# Sheet1.net
KiCad netlist of a schematic drawn in Altium Designer
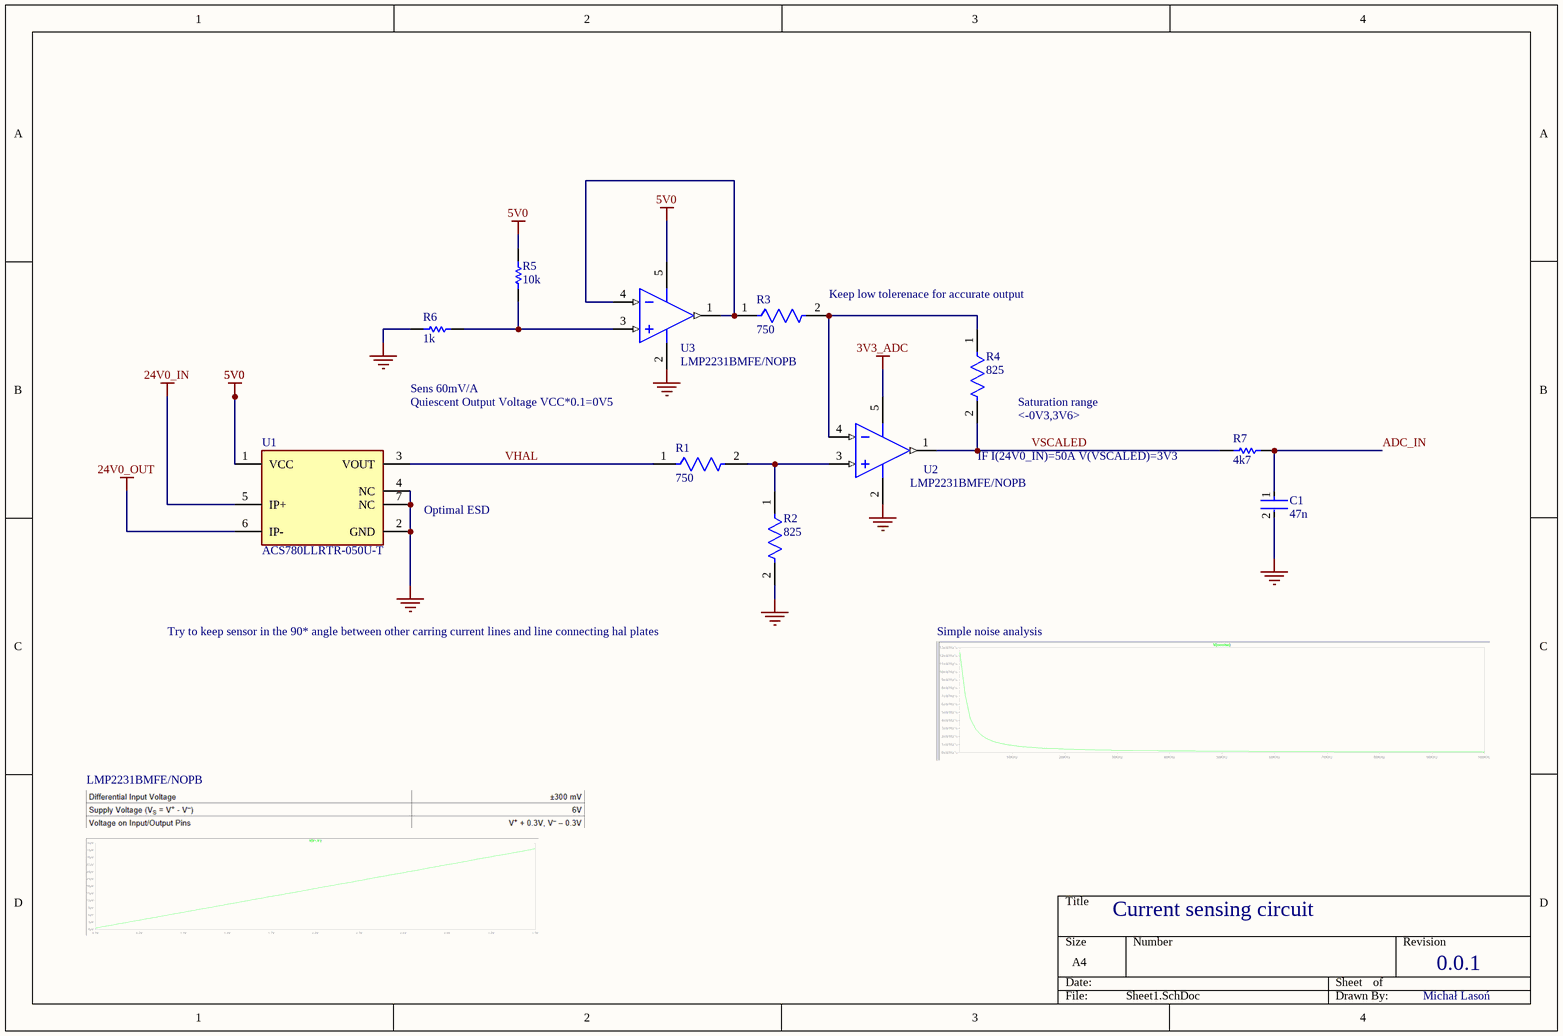
[diagram p0: Sheet1.SchDoc]

(export (version "E")
  (design (tool "Eeschema 10.0.6"))
  (components
    (comp (ref "C1")
      (value "47n")
      (footprint "FP-0805-L_2_01_0_2-W_1_25-MFG")
      (description "General Purpose Ceramic Capacitor, 0805, 47nF, 10%, X8R, 15%, 50V")
      (fields (field (name "VOLTAGE") "50V") (field (name "TOLERANCE") "10%"))
      (libsource (lib "Altium Content Vault") (part "02cd4be3c70576c341d710602a673aa"))
    )
    (comp (ref "R1")
      (value "750")
      (footprint "FP-RP73P-1J-MFG")
      (description "RES SMD 750 OHM 0.1% 1/6W 0603")
      (fields (field (name "TOLERANCE") "0.001") (field (name "MANUFACTURER PART NUMBER") "RP73PF1J750RBTDF"))
      (libsource (lib "Altium Content Vault") (part "1029c3af85768c4190bb7ad29bc67b5"))
    )
    (comp (ref "R2")
      (value "825")
      (footprint "FP-RP73P-1J-MFG")
      (description "RES SMD 825 OHM 0.1% 1/6W 0603")
      (fields
        (field (name "MANUFACTURER") "TE Connectivity")
        (field (name "OCTOPART") "https://octopart.com/rp73pf1j825rbtdf-te+connectivity-45466269")
      )
      (libsource (lib "Altium Content Vault") (part "1029c3af85768c4190bb7ad29bc67b5"))
    )
    (comp (ref "R3")
      (value "750")
      (footprint "FP-RP73P-1J-MFG")
      (description "RES SMD 750 OHM 0.1% 1/6W 0603")
      (fields (field (name "TOLERANCE") "0.001") (field (name "MANUFACTURER PART NUMBER") "RP73PF1J750RBTDF"))
      (libsource (lib "Altium Content Vault") (part "1029c3af85768c4190bb7ad29bc67b5"))
    )
    (comp (ref "R4")
      (value "825")
      (footprint "FP-RP73P-1J-MFG")
      (description "RES SMD 825 OHM 0.1% 1/6W 0603")
      (fields
        (field (name "MANUFACTURER") "TE Connectivity")
        (field (name "OCTOPART") "https://octopart.com/rp73pf1j825rbtdf-te+connectivity-45466269")
      )
      (libsource (lib "Altium Content Vault") (part "1029c3af85768c4190bb7ad29bc67b5"))
    )
    (comp (ref "R5")
      (value "10k")
      (footprint "RESC1609X50X30NL8T20")
      (description "Chip Resistor, 10 KOhm, +/- 1%, 100 mW, -55 to 155 degC, 0603 (1608 Metric), RoHS, Tape and Reel")
      (fields (field (name "MANUFACTURER") "Vishay Semiconductor"))
      (libsource (lib "Altium Content Vault") (part "RES-2"))
    )
    (comp (ref "R6")
      (value "1k")
      (footprint "RESC1608X55X30LL15T15")
      (fields (field (name "PART NUMBER") "ERJ-3EKF1001V") (field (name "MANUFACTURER") "Panasonic"))
      (libsource (lib "Altium Content Vault") (part "RES"))
    )
    (comp (ref "R7")
      (value "4k7")
      (footprint "YAGO-RC0805_M")
      (fields
        (field (name "TOLERANCE") "+/- 1%")
        (field (name "PARTNUMBER") "RC0805FR-074K7L")
        (field (name "POWER") "0.125 W")
      )
      (libsource (lib "Altium Content Vault") (part "YAGO-RES-2"))
    )
    (comp (ref "U1")
      (value "ACS780LLRTR-050U-T")
      (footprint "FP-LR-7-MFG")
      (description "HIGH-PRECISION LINEAR HALL-EFFEC")
      (libsource (lib "Altium Content Vault") (part "e7dc1a95c8c68bde7436943aa9e0c70"))
    )
    (comp (ref "U2")
      (value "LMP2231BMFE/NOPB")
      (footprint "DBV0005A_L")
      (description "Single Micropower, 1.6V, Precision Operational Amplifier with CMOS Inputs, 5-pin SOT-23, Pb-Free")
      (fields (field (name "MANUFACTURER") "Texas Instruments"))
      (libsource (lib "Altium Content Vault") (part "AMP-OPA-LM7121-5"))
    )
    (comp (ref "U3")
      (value "LMP2231BMFE/NOPB")
      (footprint "DBV0005A_L")
      (description "Single Micropower, 1.6V, Precision Operational Amplifier with CMOS Inputs, 5-pin SOT-23, Pb-Free")
      (fields (field (name "MANUFACTURER") "Texas Instruments"))
      (libsource (lib "Altium Content Vault") (part "AMP-OPA-LM7121-5"))
    )
  )
  (nets
    (net (code "1") (name "/ADC_IN") (class "Default")
      (node (ref "C1") (pin "1") (pinfunction "1_1") (pintype "passive"))
      (node (ref "R7") (pin "2") (pinfunction "2_2") (pintype "passive"))
    )
    (net (code "2") (name "/VHAL") (class "Default")
      (node (ref "R1") (pin "1") (pinfunction "1_1") (pintype "passive"))
      (node (ref "U1") (pin "3") (pinfunction "VOUT_3") (pintype "passive"))
    )
    (net (code "3") (name "/VSCALED") (class "Default")
      (node (ref "R4") (pin "2") (pinfunction "2_2") (pintype "passive"))
      (node (ref "R7") (pin "1") (pinfunction "1_1") (pintype "passive"))
      (node (ref "U2") (pin "1") (pinfunction "OUT_1") (pintype "output"))
    )
    (net (code "4") (name "3V3_ADC") (class "Default")
      (node (ref "U2") (pin "5") (pinfunction "V+_5") (pintype "power_in"))
    )
    (net (code "5") (name "5V0") (class "Default")
      (node (ref "R5") (pin "2") (pinfunction "2_2") (pintype "passive"))
      (node (ref "U1") (pin "1") (pinfunction "VCC_1") (pintype "power_in"))
      (node (ref "U3") (pin "5") (pinfunction "V+_5") (pintype "power_in"))
    )
    (net (code "6") (name "24V0_IN") (class "Default")
      (node (ref "U1") (pin "5") (pinfunction "IP+_5") (pintype "passive"))
    )
    (net (code "7") (name "24V0_OUT") (class "Default")
      (node (ref "U1") (pin "6") (pinfunction "IP-_6") (pintype "passive"))
    )
    (net (code "8") (name "GND") (class "Default")
      (node (ref "C1") (pin "2") (pinfunction "2_2") (pintype "passive"))
      (node (ref "R2") (pin "2") (pinfunction "2_2") (pintype "passive"))
      (node (ref "R6") (pin "1") (pinfunction "1_1") (pintype "passive"))
      (node (ref "U1") (pin "2") (pinfunction "GND_2") (pintype "power_in"))
      (node (ref "U1") (pin "4") (pinfunction "NC_4") (pintype "passive"))
      (node (ref "U1") (pin "7") (pinfunction "NC_7") (pintype "passive"))
      (node (ref "U2") (pin "2") (pinfunction "V-_2") (pintype "power_in"))
      (node (ref "U3") (pin "2") (pinfunction "V-_2") (pintype "power_in"))
    )
    (net (code "9") (name "Net-(U2-IN+)") (class "Default")
      (node (ref "R1") (pin "2") (pinfunction "2_2") (pintype "passive"))
      (node (ref "R2") (pin "1") (pinfunction "1_1") (pintype "passive"))
      (node (ref "U2") (pin "3") (pinfunction "IN+_3") (pintype "input"))
    )
    (net (code "10") (name "Net-(U2-IN-)") (class "Default")
      (node (ref "R3") (pin "2") (pinfunction "2_2") (pintype "passive"))
      (node (ref "R4") (pin "1") (pinfunction "1_1") (pintype "passive"))
      (node (ref "U2") (pin "4") (pinfunction "IN-_4") (pintype "input"))
    )
    (net (code "11") (name "Net-(U3-IN+)") (class "Default")
      (node (ref "R5") (pin "1") (pinfunction "1_1") (pintype "passive"))
      (node (ref "R6") (pin "2") (pinfunction "2_2") (pintype "passive"))
      (node (ref "U3") (pin "3") (pinfunction "IN+_3") (pintype "input"))
    )
    (net (code "12") (name "Net-(U3-IN-)") (class "Default")
      (node (ref "R3") (pin "1") (pinfunction "1_1") (pintype "passive"))
      (node (ref "U3") (pin "1") (pinfunction "OUT_1") (pintype "output"))
      (node (ref "U3") (pin "4") (pinfunction "IN-_4") (pintype "input"))
    )
  )
)
